# RiskChemi_Sensors.net
KiCad netlist of a schematic drawn in Altium Designer
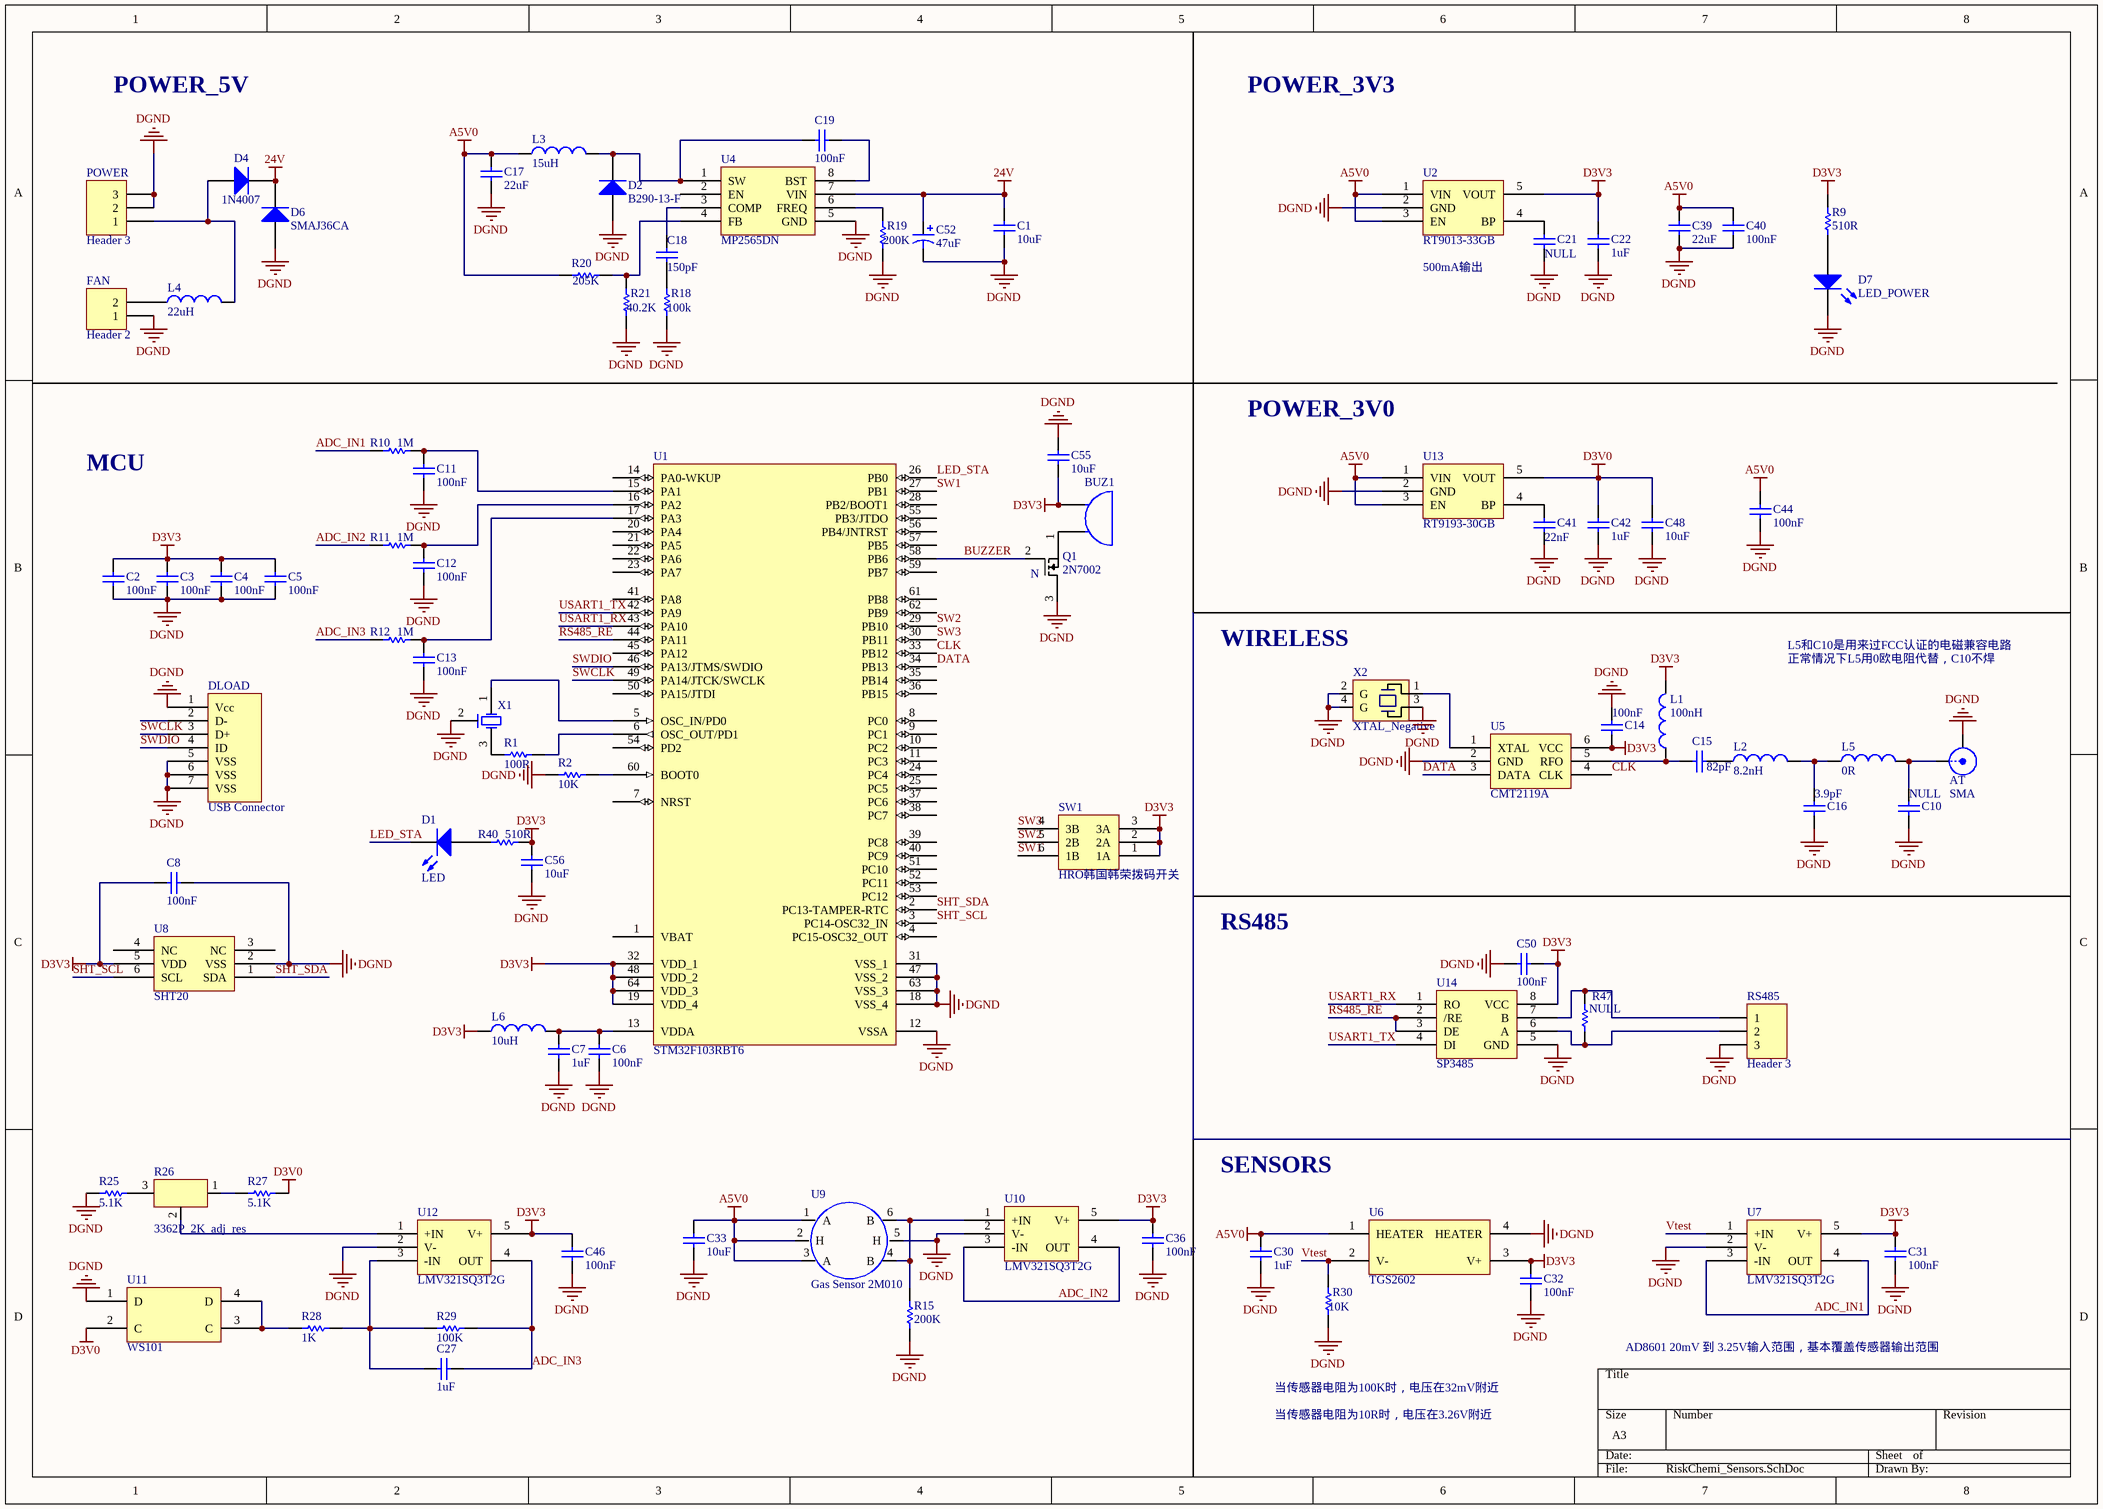
[diagram p0: RiskChemi_Sensors.SchDoc]

(export (version "E")
  (design (tool "Eeschema 10.0.6"))
  (components
    (comp (ref "AT")
      (value "SMA")
      (footprint "SMA")
      (description "SMB Straight Connector")
      (fields (field (name "PUBLISHER") "Altium Limited"))
      (libsource (lib "Miscellaneous Connectors") (part "SMB"))
    )
    (comp (ref "BUZ1")
      (value "BUZZER 0905 through hole")
      (footprint "BUZ0905")
      (description "Buzzer")
      (libsource (lib "杂元件库") (part "BUZZER"))
    )
    (comp (ref "C1")
      (value "10uF")
      (footprint "0805")
      (description "Capacitor,50V")
      (fields (field (name "PUBLISHER") "Altium Limited"))
      (libsource (lib "Miscellaneous Devices") (part "Cap"))
    )
    (comp (ref "C2")
      (value "100nF")
      (footprint "BinFeng:0603")
      (description "Capacitor")
      (fields (field (name "PUBLISHER") "Altium Limited"))
      (libsource (lib "Miscellaneous Devices") (part "Cap"))
    )
    (comp (ref "C3")
      (value "100nF")
      (footprint "BinFeng:0603")
      (description "Capacitor")
      (fields (field (name "PUBLISHER") "Altium Limited"))
      (libsource (lib "Miscellaneous Devices") (part "Cap"))
    )
    (comp (ref "C4")
      (value "100nF")
      (footprint "BinFeng:0603")
      (description "Capacitor")
      (fields (field (name "PUBLISHER") "Altium Limited"))
      (libsource (lib "Miscellaneous Devices") (part "Cap"))
    )
    (comp (ref "C5")
      (value "100nF")
      (footprint "BinFeng:0603")
      (description "Capacitor")
      (fields (field (name "PUBLISHER") "Altium Limited"))
      (libsource (lib "Miscellaneous Devices") (part "Cap"))
    )
    (comp (ref "C6")
      (value "100nF")
      (footprint "BinFeng:0603")
      (description "Capacitor")
      (fields (field (name "PUBLISHER") "Altium Limited"))
      (libsource (lib "Miscellaneous Devices") (part "Cap"))
    )
    (comp (ref "C7")
      (value "1uF")
      (footprint "BinFeng:0603")
      (description "Capacitor")
      (fields (field (name "PUBLISHER") "Altium Limited"))
      (libsource (lib "Miscellaneous Devices") (part "Cap"))
    )
    (comp (ref "C8")
      (value "100nF")
      (footprint "BinFeng:0603")
      (description "Capacitor")
      (fields (field (name "PUBLISHER") "Altium Limited"))
      (libsource (lib "Miscellaneous Devices") (part "Cap"))
    )
    (comp (ref "C10")
      (value "NULL")
      (footprint "BinFeng:0402")
      (description "Capacitor")
      (fields (field (name "PUBLISHER") "Altium Limited"))
      (libsource (lib "Miscellaneous Devices") (part "Cap"))
    )
    (comp (ref "C11")
      (value "100nF")
      (footprint "BinFeng:0603")
      (description "Capacitor")
      (fields (field (name "PUBLISHER") "Altium Limited"))
      (libsource (lib "Miscellaneous Devices") (part "Cap"))
    )
    (comp (ref "C12")
      (value "100nF")
      (footprint "BinFeng:0603")
      (description "Capacitor")
      (fields (field (name "PUBLISHER") "Altium Limited"))
      (libsource (lib "Miscellaneous Devices") (part "Cap"))
    )
    (comp (ref "C13")
      (value "100nF")
      (footprint "BinFeng:0603")
      (description "Capacitor")
      (fields (field (name "PUBLISHER") "Altium Limited"))
      (libsource (lib "Miscellaneous Devices") (part "Cap"))
    )
    (comp (ref "C14")
      (value "100nF")
      (footprint "BinFeng:0402")
      (description "Capacitor")
      (fields (field (name "PUBLISHER") "Altium Limited"))
      (libsource (lib "Miscellaneous Devices") (part "Cap"))
    )
    (comp (ref "C15")
      (value "82pF")
      (footprint "BinFeng:0402")
      (description "Capacitor")
      (fields (field (name "PUBLISHER") "Altium Limited"))
      (libsource (lib "Miscellaneous Devices") (part "Cap"))
    )
    (comp (ref "C16")
      (value "3.9pF")
      (footprint "BinFeng:0402")
      (description "Capacitor")
      (fields (field (name "PUBLISHER") "Altium Limited"))
      (libsource (lib "Miscellaneous Devices") (part "Cap"))
    )
    (comp (ref "C17")
      (value "22uF")
      (footprint "0805")
      (description "Capacitor,50V")
      (fields (field (name "PUBLISHER") "Altium Limited"))
      (libsource (lib "Miscellaneous Devices") (part "Cap"))
    )
    (comp (ref "C18")
      (value "150pF")
      (footprint "BinFeng:0603")
      (description "Capacitor")
      (fields (field (name "PUBLISHER") "Altium Limited"))
      (libsource (lib "Miscellaneous Devices") (part "Cap"))
    )
    (comp (ref "C19")
      (value "100nF")
      (footprint "BinFeng:0603")
      (description "Capacitor")
      (fields (field (name "PUBLISHER") "Altium Limited"))
      (libsource (lib "Miscellaneous Devices") (part "Cap"))
    )
    (comp (ref "C21")
      (value "NULL")
      (footprint "BinFeng:0402")
      (description "Capacitor")
      (fields (field (name "PUBLISHER") "Altium Limited"))
      (libsource (lib "Miscellaneous Devices") (part "Cap"))
    )
    (comp (ref "C22")
      (value "1uF")
      (footprint "BinFeng:0402")
      (description "Capacitor")
      (fields (field (name "PUBLISHER") "Altium Limited"))
      (libsource (lib "Miscellaneous Devices") (part "Cap"))
    )
    (comp (ref "C27")
      (value "1uF")
      (footprint "BinFeng:0603")
      (description "Capacitor")
      (fields (field (name "PUBLISHER") "Altium Limited"))
      (libsource (lib "Miscellaneous Devices") (part "Cap"))
    )
    (comp (ref "C30")
      (value "1uF")
      (footprint "BinFeng:0603")
      (description "Capacitor")
      (fields (field (name "PUBLISHER") "Altium Limited"))
      (libsource (lib "Miscellaneous Devices") (part "Cap"))
    )
    (comp (ref "C31")
      (value "100nF")
      (footprint "BinFeng:0603")
      (description "Capacitor")
      (fields (field (name "PUBLISHER") "Altium Limited"))
      (libsource (lib "Miscellaneous Devices") (part "Cap"))
    )
    (comp (ref "C32")
      (value "100nF")
      (footprint "BinFeng:0603")
      (description "Capacitor")
      (fields (field (name "PUBLISHER") "Altium Limited"))
      (libsource (lib "Miscellaneous Devices") (part "Cap"))
    )
    (comp (ref "C33")
      (value "10uF")
      (footprint "0805")
      (description "Capacitor")
      (fields (field (name "PUBLISHER") "Altium Limited"))
      (libsource (lib "Miscellaneous Devices") (part "Cap"))
    )
    (comp (ref "C36")
      (value "100nF")
      (footprint "BinFeng:0603")
      (description "Capacitor")
      (fields (field (name "PUBLISHER") "Altium Limited"))
      (libsource (lib "Miscellaneous Devices") (part "Cap"))
    )
    (comp (ref "C39")
      (value "22uF")
      (footprint "1206")
      (description "Capacitor")
      (fields (field (name "PUBLISHER") "Altium Limited"))
      (libsource (lib "Miscellaneous Devices") (part "Cap"))
    )
    (comp (ref "C40")
      (value "100nF")
      (footprint "BinFeng:0402")
      (description "Capacitor")
      (fields (field (name "PUBLISHER") "Altium Limited"))
      (libsource (lib "Miscellaneous Devices") (part "Cap"))
    )
    (comp (ref "C41")
      (value "22nF")
      (footprint "BinFeng:0402")
      (description "Capacitor")
      (fields (field (name "PUBLISHER") "Altium Limited"))
      (libsource (lib "Miscellaneous Devices") (part "Cap"))
    )
    (comp (ref "C42")
      (value "1uF")
      (footprint "BinFeng:0402")
      (description "Capacitor")
      (fields (field (name "PUBLISHER") "Altium Limited"))
      (libsource (lib "Miscellaneous Devices") (part "Cap"))
    )
    (comp (ref "C44")
      (value "100nF")
      (footprint "BinFeng:0402")
      (description "Capacitor")
      (fields (field (name "PUBLISHER") "Altium Limited"))
      (libsource (lib "Miscellaneous Devices") (part "Cap"))
    )
    (comp (ref "C46")
      (value "100nF")
      (footprint "BinFeng:0603")
      (description "Capacitor")
      (fields (field (name "PUBLISHER") "Altium Limited"))
      (libsource (lib "Miscellaneous Devices") (part "Cap"))
    )
    (comp (ref "C48")
      (value "10uF")
      (footprint "0805")
      (description "Capacitor")
      (fields (field (name "PUBLISHER") "Altium Limited"))
      (libsource (lib "Miscellaneous Devices") (part "Cap"))
    )
    (comp (ref "C50")
      (value "100nF")
      (footprint "BinFeng:0603")
      (description "Capacitor")
      (fields (field (name "PUBLISHER") "Altium Limited"))
      (libsource (lib "Miscellaneous Devices") (part "Cap"))
    )
    (comp (ref "C52")
      (value "47uF")
      (footprint "cap_pol_8*10.2")
      (description "Polarized Capacitor (Radial)")
      (fields (field (name "PUBLISHER") "Altium Limited"))
      (libsource (lib "Miscellaneous Devices") (part "Cap Pol1"))
    )
    (comp (ref "C55")
      (value "10uF")
      (footprint "0805")
      (description "Capacitor")
      (fields (field (name "PUBLISHER") "Altium Limited"))
      (libsource (lib "Miscellaneous Devices") (part "Cap"))
    )
    (comp (ref "C56")
      (value "10uF")
      (footprint "0805")
      (description "Capacitor")
      (fields (field (name "PUBLISHER") "Altium Limited"))
      (libsource (lib "Miscellaneous Devices") (part "Cap"))
    )
    (comp (ref "D1")
      (value "LED")
      (footprint "1206_LED")
      (description "Typical INFRARED GaAs LED")
      (fields (field (name "PUBLISHER") "Altium Limited"))
      (libsource (lib "Miscellaneous Devices") (part "LED0"))
    )
    (comp (ref "D2")
      (value "B290-13-F")
      (footprint "B290")
      (description "Default Diode")
      (fields (field (name "PUBLISHER") "Altium Limited"))
      (libsource (lib "Miscellaneous Devices") (part "Diode"))
    )
    (comp (ref "D4")
      (value "1N4007")
      (footprint "6032_pol")
      (description "1 Amp General Purpose Rectifier")
      (fields (field (name "PUBLISHER") "Altium Limited"))
      (libsource (lib "Miscellaneous Devices") (part "Diode 1N4007"))
    )
    (comp (ref "D6")
      (value "SMAJ36CA")
      (footprint "B290")
      (description "1 Amp General Purpose Rectifier")
      (fields (field (name "PUBLISHER") "Altium Limited"))
      (libsource (lib "Miscellaneous Devices") (part "Diode 1N4007"))
    )
    (comp (ref "D7")
      (value "LED_POWER")
      (footprint "1206_LED")
      (description "Typical INFRARED GaAs LED")
      (fields (field (name "PUBLISHER") "Altium Limited"))
      (libsource (lib "Miscellaneous Devices") (part "LED0"))
    )
    (comp (ref "DLOAD")
      (value "USB Connector")
      (footprint "Mini_USB")
      (libsource (lib "BinFeng_Connectors") (part "Component_1"))
    )
    (comp (ref "FAN")
      (value "Header 2")
      (footprint "HDR1X2")
      (description "Header, 2-Pin")
      (fields (field (name "PUBLISHER") "Altium Limited"))
      (libsource (lib "Miscellaneous Connectors") (part "Header 2"))
    )
    (comp (ref "L1")
      (value "100nH")
      (footprint "0603C")
      (description "Inductor")
      (fields (field (name "PUBLISHER") "Altium Limited"))
      (libsource (lib "Miscellaneous Devices") (part "Inductor"))
    )
    (comp (ref "L2")
      (value "8.2nH")
      (footprint "0603C")
      (description "Inductor")
      (fields (field (name "PUBLISHER") "Altium Limited"))
      (libsource (lib "Miscellaneous Devices") (part "Inductor"))
    )
    (comp (ref "L3")
      (value "15uH")
      (footprint "4*4 Inductor")
      (description "Inductor, 1A")
      (fields (field (name "PUBLISHER") "Altium Limited"))
      (libsource (lib "Miscellaneous Devices") (part "Inductor"))
    )
    (comp (ref "L4")
      (value "22uH")
      (footprint "10*10Inductor")
      (description "Inductor, 1A")
      (fields (field (name "PUBLISHER") "Altium Limited"))
      (libsource (lib "Miscellaneous Devices") (part "Inductor"))
    )
    (comp (ref "L5")
      (value "0R")
      (footprint "0603C")
      (description "Inductor")
      (fields (field (name "PUBLISHER") "Altium Limited"))
      (libsource (lib "Miscellaneous Devices") (part "Inductor"))
    )
    (comp (ref "L6")
      (value "10uH")
      (footprint "0805")
      (description "Inductor")
      (fields (field (name "PUBLISHER") "Altium Limited"))
      (libsource (lib "Miscellaneous Devices") (part "Inductor"))
    )
    (comp (ref "POWER")
      (value "Header 3")
      (footprint "KR_1x2H")
      (description "Header, 3-Pin")
      (fields (field (name "PUBLISHER") "Altium Limited"))
      (libsource (lib "Miscellaneous Connectors") (part "Header 3"))
    )
    (comp (ref "Q1") (value "2N7002") (footprint "2N7002") (libsource (lib "seeder") (part "N-MOSFET")))
    (comp (ref "R1")
      (value "100R")
      (footprint "BinFeng:0603")
      (description "Resistor")
      (fields (field (name "PUBLISHER") "Altium Limited"))
      (libsource (lib "Miscellaneous Devices") (part "Res1"))
    )
    (comp (ref "R2")
      (value "10K")
      (footprint "BinFeng:0603")
      (description "Resistor")
      (fields (field (name "PUBLISHER") "Altium Limited"))
      (libsource (lib "Miscellaneous Devices") (part "Res1"))
    )
    (comp (ref "R9")
      (value "510R")
      (footprint "BinFeng:0603")
      (description "Resistor")
      (fields (field (name "PUBLISHER") "Altium Limited"))
      (libsource (lib "Miscellaneous Devices") (part "Res1"))
    )
    (comp (ref "R10")
      (value "1M")
      (footprint "BinFeng:0603")
      (description "Resistor")
      (fields (field (name "PUBLISHER") "Altium Limited"))
      (libsource (lib "Miscellaneous Devices") (part "Res1"))
    )
    (comp (ref "R11")
      (value "1M")
      (footprint "BinFeng:0603")
      (description "Resistor")
      (fields (field (name "PUBLISHER") "Altium Limited"))
      (libsource (lib "Miscellaneous Devices") (part "Res1"))
    )
    (comp (ref "R12")
      (value "1M")
      (footprint "BinFeng:0603")
      (description "Resistor")
      (fields (field (name "PUBLISHER") "Altium Limited"))
      (libsource (lib "Miscellaneous Devices") (part "Res1"))
    )
    (comp (ref "R15")
      (value "200K")
      (footprint "BinFeng:0603C")
      (description "Resistor")
      (fields (field (name "Comment") "Res1") (field (name "PUBLISHER") "Altium Limited"))
      (libsource (lib "Miscellaneous Devices") (part "Res1"))
    )
    (comp (ref "R18")
      (value "100k")
      (footprint "BinFeng:0603")
      (description "Resistor")
      (fields (field (name "PUBLISHER") "Altium Limited"))
      (libsource (lib "Miscellaneous Devices") (part "Res1"))
    )
    (comp (ref "R19")
      (value "200K")
      (footprint "BinFeng:0402")
      (description "Resistor")
      (fields (field (name "PUBLISHER") "Altium Limited"))
      (libsource (lib "Miscellaneous Devices") (part "Res1"))
    )
    (comp (ref "R20")
      (value "205K")
      (footprint "BinFeng:0603")
      (description "Resistor")
      (fields (field (name "PUBLISHER") "Altium Limited"))
      (libsource (lib "Miscellaneous Devices") (part "Res1"))
    )
    (comp (ref "R21")
      (value "40.2K")
      (footprint "BinFeng:0603")
      (description "Resistor")
      (fields (field (name "PUBLISHER") "Altium Limited"))
      (libsource (lib "Miscellaneous Devices") (part "Res1"))
    )
    (comp (ref "R25")
      (value "5.1K")
      (footprint "BinFeng:0603")
      (description "Resistor")
      (fields (field (name "PUBLISHER") "Altium Limited"))
      (libsource (lib "Miscellaneous Devices") (part "Res1"))
    )
    (comp (ref "R26")
      (value "3362P_2K_adj_res")
      (footprint "res_adj")
      (libsource (lib "BinFeng_IC") (part "res_adj"))
    )
    (comp (ref "R27")
      (value "5.1K")
      (footprint "BinFeng:0603")
      (description "Resistor")
      (fields (field (name "PUBLISHER") "Altium Limited"))
      (libsource (lib "Miscellaneous Devices") (part "Res1"))
    )
    (comp (ref "R28")
      (value "1K")
      (footprint "BinFeng:0603")
      (description "Resistor")
      (fields (field (name "PUBLISHER") "Altium Limited"))
      (libsource (lib "Miscellaneous Devices") (part "Res1"))
    )
    (comp (ref "R29")
      (value "100K")
      (footprint "BinFeng:0603")
      (description "Resistor")
      (fields (field (name "PUBLISHER") "Altium Limited"))
      (libsource (lib "Miscellaneous Devices") (part "Res1"))
    )
    (comp (ref "R30")
      (value "10K")
      (footprint "BinFeng:0603")
      (description "Resistor")
      (fields (field (name "PUBLISHER") "Altium Limited"))
      (libsource (lib "Miscellaneous Devices") (part "Res1"))
    )
    (comp (ref "R40")
      (value "510R")
      (footprint "BinFeng:0603")
      (description "Resistor")
      (fields (field (name "PUBLISHER") "Altium Limited"))
      (libsource (lib "Miscellaneous Devices") (part "Res1"))
    )
    (comp (ref "R47")
      (value "NULL")
      (footprint "BinFeng:0603")
      (description "Resistor")
      (fields (field (name "PUBLISHER") "Altium Limited"))
      (libsource (lib "Miscellaneous Devices") (part "Res1"))
    )
    (comp (ref "RS485")
      (value "Header 3")
      (footprint "KR_1x2H")
      (description "Header, 3-Pin")
      (fields (field (name "PUBLISHER") "Altium Limited"))
      (libsource (lib "") (part "Header 3_1"))
    )
    (comp (ref "SW1")
      (value "HRO韩国韩荣拨码开关")
      (footprint "SW_6P_HRO")
      (libsource (lib "BinFeng_IC") (part "SW_6P"))
    )
    (comp (ref "U1")
      (value "STM32F103RBT6")
      (footprint "LQFP64_N")
      (description "STM32 ARM-based 32-bit MCU with 64 Kbytes Flash, 64-pin LQFP, Industrial Temperature")
      (fields (field (name "PUBLISHER") "Altium Limited"))
      (libsource (lib "ST Microcontroller 32-Bit STM32") (part "STM32F103R8T6"))
    )
    (comp (ref "U2")
      (value "RT9013-33GB")
      (footprint "SOT-23-5")
      (libsource (lib "BinFeng_IC") (part "RT9193"))
    )
    (comp (ref "U4")
      (value "MP2565DN")
      (footprint "so-8")
      (description "DCDC 4.5V~28V input 1.8V ~5V output low power")
      (libsource (lib "BinFeng_IC") (part "MP1584"))
    )
    (comp (ref "U5")
      (value "CMT2119A")
      (footprint "sot23-6")
      (libsource (lib "BinFeng_IC") (part "CMT2119A"))
    )
    (comp (ref "U6")
      (value "TGS2602")
      (footprint "Gas Sensor TGS2602 Slot")
      (description "VOC sensor")
      (libsource (lib "BinFeng_IC") (part "TGS2602"))
    )
    (comp (ref "U7")
      (value "LMV321SQ3T2G")
      (footprint "SC-70-5")
      (libsource (lib "BinFeng_IC") (part "LMV321SQ3T2G"))
    )
    (comp (ref "U8") (value "SHT20") (footprint "SHT20") (libsource (lib "BinFeng_IC") (part "SHT20")))
    (comp (ref "U9")
      (value "Gas Sensor 2M010")
      (footprint "Gas Sensor 2M010 Slot")
      (libsource (lib "BinFeng_IC") (part "Gas Sensor"))
    )
    (comp (ref "U10")
      (value "LMV321SQ3T2G")
      (footprint "SC-70-5")
      (libsource (lib "BinFeng_IC") (part "LMV321SQ3T2G"))
    )
    (comp (ref "U11")
      (value "WS101")
      (footprint "Gas_Sensor_WS101_Slot")
      (libsource (lib "BinFeng_IC") (part "Gas Sensor_WS101"))
    )
    (comp (ref "U12")
      (value "LMV321SQ3T2G")
      (footprint "SC-70-5")
      (libsource (lib "BinFeng_IC") (part "LMV321SQ3T2G"))
    )
    (comp (ref "U13")
      (value "RT9193-30GB")
      (footprint "SOT-23-5")
      (libsource (lib "BinFeng_IC") (part "RT9193"))
    )
    (comp (ref "U14") (value "SP3485") (footprint "SO-8N") (libsource (lib "BinFeng_IC") (part "SP3485")))
    (comp (ref "X1") (value "8M smd") (footprint "8Mhz_XTAL") (libsource (lib "Schlib1") (part "8M smd")))
    (comp (ref "X2")
      (value "XTAL_Negative")
      (footprint "XTAL3225")
      (libsource (lib "BinFeng_IC") (part "XTAL_Negative"))
    )
  )
  (nets
    (net (code "1") (name "/ADC_IN1") (class "Default")
      (node (ref "R10") (pin "1") (pinfunction "1_1") (pintype "passive"))
      (node (ref "U7") (pin "3") (pinfunction "-IN_3") (pintype "passive"))
      (node (ref "U7") (pin "4") (pinfunction "OUT_4") (pintype "passive"))
    )
    (net (code "2") (name "/ADC_IN2") (class "Default")
      (node (ref "R11") (pin "1") (pinfunction "1_1") (pintype "passive"))
      (node (ref "U10") (pin "3") (pinfunction "-IN_3") (pintype "passive"))
      (node (ref "U10") (pin "4") (pinfunction "OUT_4") (pintype "passive"))
    )
    (net (code "3") (name "/ADC_IN3") (class "Default")
      (node (ref "C27") (pin "1") (pinfunction "1_1") (pintype "passive"))
      (node (ref "R12") (pin "1") (pinfunction "1_1") (pintype "passive"))
      (node (ref "R29") (pin "2") (pinfunction "2_2") (pintype "passive"))
      (node (ref "U12") (pin "4") (pinfunction "OUT_4") (pintype "passive"))
    )
    (net (code "4") (name "/BUZZER") (class "Default")
      (node (ref "Q1") (pin "2") (pinfunction "G_2") (pintype "passive"))
      (node (ref "U1") (pin "58") (pinfunction "PB6_58") (pintype "bidirectional"))
    )
    (net (code "5") (name "/CLK") (class "Default")
      (node (ref "U1") (pin "33") (pinfunction "PB12_33") (pintype "bidirectional"))
      (node (ref "U5") (pin "4") (pinfunction "CLK_4") (pintype "passive"))
    )
    (net (code "6") (name "/DATA") (class "Default")
      (node (ref "U1") (pin "34") (pinfunction "PB13_34") (pintype "bidirectional"))
      (node (ref "U5") (pin "3") (pinfunction "DATA_3") (pintype "passive"))
    )
    (net (code "7") (name "/LED_STA") (class "Default")
      (node (ref "D1") (pin "2") (pinfunction "K_2") (pintype "passive"))
      (node (ref "U1") (pin "26") (pinfunction "PB0_26") (pintype "bidirectional"))
    )
    (net (code "8") (name "/RS485_RE") (class "Default")
      (node (ref "U1") (pin "44") (pinfunction "PA11_44") (pintype "bidirectional"))
      (node (ref "U14") (pin "2") (pinfunction "/RE_2") (pintype "passive"))
      (node (ref "U14") (pin "3") (pinfunction "DE_3") (pintype "passive"))
    )
    (net (code "9") (name "/SHT_SCL") (class "Default")
      (node (ref "U1") (pin "3") (pinfunction "PC14-OSC32_IN_3") (pintype "bidirectional"))
      (node (ref "U8") (pin "6") (pinfunction "SCL_6") (pintype "passive"))
    )
    (net (code "10") (name "/SHT_SDA") (class "Default")
      (node (ref "U1") (pin "2") (pinfunction "PC13-TAMPER-RTC_2") (pintype "bidirectional"))
      (node (ref "U8") (pin "1") (pinfunction "SDA_1") (pintype "passive"))
    )
    (net (code "11") (name "/SW1") (class "Default")
      (node (ref "SW1") (pin "6") (pinfunction "1B_6") (pintype "passive"))
      (node (ref "U1") (pin "27") (pinfunction "PB1_27") (pintype "bidirectional"))
    )
    (net (code "12") (name "/SW2") (class "Default")
      (node (ref "SW1") (pin "5") (pinfunction "2B_5") (pintype "passive"))
      (node (ref "U1") (pin "29") (pinfunction "PB10_29") (pintype "bidirectional"))
    )
    (net (code "13") (name "/SW3") (class "Default")
      (node (ref "SW1") (pin "4") (pinfunction "3B_4") (pintype "passive"))
      (node (ref "U1") (pin "30") (pinfunction "PB11_30") (pintype "bidirectional"))
    )
    (net (code "14") (name "/SWCLK") (class "Default")
      (node (ref "DLOAD") (pin "3") (pinfunction "D+_3") (pintype "passive"))
      (node (ref "U1") (pin "49") (pinfunction "PA14/JTCK/SWCLK_49") (pintype "bidirectional"))
    )
    (net (code "15") (name "/SWDIO") (class "Default")
      (node (ref "DLOAD") (pin "4") (pinfunction "ID_4") (pintype "passive"))
      (node (ref "U1") (pin "46") (pinfunction "PA13/JTMS/SWDIO_46") (pintype "bidirectional"))
    )
    (net (code "16") (name "/USART1_RX") (class "Default")
      (node (ref "U1") (pin "43") (pinfunction "PA10_43") (pintype "bidirectional"))
      (node (ref "U14") (pin "1") (pinfunction "RO_1") (pintype "passive"))
    )
    (net (code "17") (name "/USART1_TX") (class "Default")
      (node (ref "U1") (pin "42") (pinfunction "PA9_42") (pintype "bidirectional"))
      (node (ref "U14") (pin "4") (pinfunction "DI_4") (pintype "passive"))
    )
    (net (code "18") (name "/Vtest") (class "Default")
      (node (ref "R30") (pin "2") (pinfunction "2_2") (pintype "passive"))
      (node (ref "U6") (pin "2") (pinfunction "V-_2") (pintype "passive"))
      (node (ref "U7") (pin "1") (pinfunction "+IN_1") (pintype "passive"))
    )
    (net (code "19") (name "24V") (class "Default")
      (node (ref "C1") (pin "2") (pinfunction "2_2") (pintype "passive"))
      (node (ref "C52") (pin "1") (pinfunction "1_1") (pintype "passive"))
      (node (ref "D4") (pin "2") (pinfunction "K_2") (pintype "passive"))
      (node (ref "D6") (pin "2") (pinfunction "K_2") (pintype "passive"))
      (node (ref "U4") (pin "7") (pinfunction "VIN_7") (pintype "passive"))
    )
    (net (code "20") (name "A5V0") (class "Default")
      (node (ref "C17") (pin "2") (pinfunction "2_2") (pintype "passive"))
      (node (ref "C30") (pin "2") (pinfunction "2_2") (pintype "passive"))
      (node (ref "C33") (pin "2") (pinfunction "2_2") (pintype "passive"))
      (node (ref "C39") (pin "1") (pinfunction "1_1") (pintype "passive"))
      (node (ref "C40") (pin "2") (pinfunction "2_2") (pintype "passive"))
      (node (ref "C44") (pin "2") (pinfunction "2_2") (pintype "passive"))
      (node (ref "L3") (pin "1") (pinfunction "1_1") (pintype "passive"))
      (node (ref "R20") (pin "2") (pinfunction "2_2") (pintype "passive"))
      (node (ref "U13") (pin "1") (pinfunction "VIN_1") (pintype "passive"))
      (node (ref "U13") (pin "3") (pinfunction "EN_3") (pintype "passive"))
      (node (ref "U2") (pin "1") (pinfunction "VIN_1") (pintype "passive"))
      (node (ref "U2") (pin "3") (pinfunction "EN_3") (pintype "passive"))
      (node (ref "U6") (pin "1") (pinfunction "HEATER_1") (pintype "passive"))
      (node (ref "U9") (pin "1") (pinfunction "A_1") (pintype "passive"))
      (node (ref "U9") (pin "2") (pinfunction "H_2") (pintype "passive"))
      (node (ref "U9") (pin "3") (pinfunction "A_3") (pintype "passive"))
    )
    (net (code "21") (name "D3V0") (class "Default")
      (node (ref "C42") (pin "2") (pinfunction "2_2") (pintype "passive"))
      (node (ref "C48") (pin "2") (pinfunction "2_2") (pintype "passive"))
      (node (ref "R27") (pin "2") (pinfunction "2_2") (pintype "passive"))
      (node (ref "U11") (pin "2") (pinfunction "C_2") (pintype "passive"))
      (node (ref "U13") (pin "5") (pinfunction "VOUT_5") (pintype "passive"))
    )
    (net (code "22") (name "D3V3") (class "Default")
      (node (ref "BUZ1") (pin "1") (pinfunction "A_1") (pintype "passive"))
      (node (ref "C14") (pin "2") (pinfunction "2_2") (pintype "passive"))
      (node (ref "C2") (pin "2") (pinfunction "2_2") (pintype "passive"))
      (node (ref "C22") (pin "2") (pinfunction "2_2") (pintype "passive"))
      (node (ref "C3") (pin "2") (pinfunction "2_2") (pintype "passive"))
      (node (ref "C31") (pin "2") (pinfunction "2_2") (pintype "passive"))
      (node (ref "C32") (pin "2") (pinfunction "2_2") (pintype "passive"))
      (node (ref "C36") (pin "2") (pinfunction "2_2") (pintype "passive"))
      (node (ref "C4") (pin "2") (pinfunction "2_2") (pintype "passive"))
      (node (ref "C46") (pin "2") (pinfunction "2_2") (pintype "passive"))
      (node (ref "C5") (pin "2") (pinfunction "2_2") (pintype "passive"))
      (node (ref "C50") (pin "2") (pinfunction "2_2") (pintype "passive"))
      (node (ref "C55") (pin "2") (pinfunction "2_2") (pintype "passive"))
      (node (ref "C56") (pin "2") (pinfunction "2_2") (pintype "passive"))
      (node (ref "C8") (pin "2") (pinfunction "2_2") (pintype "passive"))
      (node (ref "L1") (pin "2") (pinfunction "2_2") (pintype "passive"))
      (node (ref "L6") (pin "1") (pinfunction "1_1") (pintype "passive"))
      (node (ref "R40") (pin "2") (pinfunction "2_2") (pintype "passive"))
      (node (ref "R9") (pin "2") (pinfunction "2_2") (pintype "passive"))
      (node (ref "SW1") (pin "1") (pinfunction "1A_1") (pintype "passive"))
      (node (ref "SW1") (pin "2") (pinfunction "2A_2") (pintype "passive"))
      (node (ref "SW1") (pin "3") (pinfunction "3A_3") (pintype "passive"))
      (node (ref "U1") (pin "19") (pinfunction "VDD_4_19") (pintype "power_in"))
      (node (ref "U1") (pin "32") (pinfunction "VDD_1_32") (pintype "power_in"))
      (node (ref "U1") (pin "48") (pinfunction "VDD_2_48") (pintype "power_in"))
      (node (ref "U1") (pin "64") (pinfunction "VDD_3_64") (pintype "power_in"))
      (node (ref "U10") (pin "5") (pinfunction "V+_5") (pintype "passive"))
      (node (ref "U12") (pin "5") (pinfunction "V+_5") (pintype "passive"))
      (node (ref "U14") (pin "8") (pinfunction "VCC_8") (pintype "passive"))
      (node (ref "U2") (pin "5") (pinfunction "VOUT_5") (pintype "passive"))
      (node (ref "U5") (pin "6") (pinfunction "VCC_6") (pintype "passive"))
      (node (ref "U6") (pin "3") (pinfunction "V+_3") (pintype "passive"))
      (node (ref "U7") (pin "5") (pinfunction "V+_5") (pintype "passive"))
      (node (ref "U8") (pin "5") (pinfunction "VDD_5") (pintype "passive"))
    )
    (net (code "23") (name "DGND") (class "Default")
      (node (ref "AT") (pin "2") (pinfunction "Y_2") (pintype "passive"))
      (node (ref "C1") (pin "1") (pinfunction "1_1") (pintype "passive"))
      (node (ref "C10") (pin "1") (pinfunction "1_1") (pintype "passive"))
      (node (ref "C11") (pin "2") (pinfunction "2_2") (pintype "passive"))
      (node (ref "C12") (pin "1") (pinfunction "1_1") (pintype "passive"))
      (node (ref "C13") (pin "1") (pinfunction "1_1") (pintype "passive"))
      (node (ref "C14") (pin "1") (pinfunction "1_1") (pintype "passive"))
      (node (ref "C16") (pin "1") (pinfunction "1_1") (pintype "passive"))
      (node (ref "C17") (pin "1") (pinfunction "1_1") (pintype "passive"))
      (node (ref "C2") (pin "1") (pinfunction "1_1") (pintype "passive"))
      (node (ref "C21") (pin "1") (pinfunction "1_1") (pintype "passive"))
      (node (ref "C22") (pin "1") (pinfunction "1_1") (pintype "passive"))
      (node (ref "C3") (pin "1") (pinfunction "1_1") (pintype "passive"))
      (node (ref "C30") (pin "1") (pinfunction "1_1") (pintype "passive"))
      (node (ref "C31") (pin "1") (pinfunction "1_1") (pintype "passive"))
      (node (ref "C32") (pin "1") (pinfunction "1_1") (pintype "passive"))
      (node (ref "C33") (pin "1") (pinfunction "1_1") (pintype "passive"))
      (node (ref "C36") (pin "1") (pinfunction "1_1") (pintype "passive"))
      (node (ref "C39") (pin "2") (pinfunction "2_2") (pintype "passive"))
      (node (ref "C4") (pin "1") (pinfunction "1_1") (pintype "passive"))
      (node (ref "C40") (pin "1") (pinfunction "1_1") (pintype "passive"))
      (node (ref "C41") (pin "1") (pinfunction "1_1") (pintype "passive"))
      (node (ref "C42") (pin "1") (pinfunction "1_1") (pintype "passive"))
      (node (ref "C44") (pin "1") (pinfunction "1_1") (pintype "passive"))
      (node (ref "C46") (pin "1") (pinfunction "1_1") (pintype "passive"))
      (node (ref "C48") (pin "1") (pinfunction "1_1") (pintype "passive"))
      (node (ref "C5") (pin "1") (pinfunction "1_1") (pintype "passive"))
      (node (ref "C50") (pin "1") (pinfunction "1_1") (pintype "passive"))
      (node (ref "C52") (pin "2") (pinfunction "2_2") (pintype "passive"))
      (node (ref "C55") (pin "1") (pinfunction "1_1") (pintype "passive"))
      (node (ref "C56") (pin "1") (pinfunction "1_1") (pintype "passive"))
      (node (ref "C6") (pin "1") (pinfunction "1_1") (pintype "passive"))
      (node (ref "C7") (pin "1") (pinfunction "1_1") (pintype "passive"))
      (node (ref "C8") (pin "1") (pinfunction "1_1") (pintype "passive"))
      (node (ref "D2") (pin "1") (pinfunction "A_1") (pintype "passive"))
      (node (ref "D6") (pin "1") (pinfunction "A_1") (pintype "passive"))
      (node (ref "D7") (pin "2") (pinfunction "K_2") (pintype "passive"))
      (node (ref "DLOAD") (pin "1") (pinfunction "Vcc_1") (pintype "passive"))
      (node (ref "DLOAD") (pin "5") (pinfunction "VSS_5") (pintype "passive"))
      (node (ref "DLOAD") (pin "6") (pinfunction "VSS_6") (pintype "passive"))
      (node (ref "DLOAD") (pin "7") (pinfunction "VSS_7") (pintype "passive"))
      (node (ref "FAN") (pin "1") (pinfunction "1_1") (pintype "passive"))
      (node (ref "POWER") (pin "2") (pinfunction "2_2") (pintype "passive"))
      (node (ref "POWER") (pin "3") (pinfunction "3_3") (pintype "passive"))
      (node (ref "Q1") (pin "3") (pinfunction "S_3") (pintype "passive"))
      (node (ref "R15") (pin "2") (pinfunction "2_2") (pintype "passive"))
      (node (ref "R18") (pin "1") (pinfunction "1_1") (pintype "passive"))
      (node (ref "R19") (pin "1") (pinfunction "1_1") (pintype "passive"))
      (node (ref "R2") (pin "1") (pinfunction "1_1") (pintype "passive"))
      (node (ref "R21") (pin "1") (pinfunction "1_1") (pintype "passive"))
      (node (ref "R25") (pin "1") (pinfunction "1_1") (pintype "passive"))
      (node (ref "R30") (pin "1") (pinfunction "1_1") (pintype "passive"))
      (node (ref "RS485") (pin "3") (pinfunction "3_3") (pintype "passive"))
      (node (ref "U1") (pin "12") (pinfunction "VSSA_12") (pintype "power_in"))
      (node (ref "U1") (pin "18") (pinfunction "VSS_4_18") (pintype "power_in"))
      (node (ref "U1") (pin "31") (pinfunction "VSS_1_31") (pintype "power_in"))
      (node (ref "U1") (pin "47") (pinfunction "VSS_2_47") (pintype "power_in"))
      (node (ref "U1") (pin "63") (pinfunction "VSS_3_63") (pintype "power_in"))
      (node (ref "U10") (pin "2") (pinfunction "V-_2") (pintype "passive"))
      (node (ref "U11") (pin "1") (pinfunction "D_1") (pintype "passive"))
      (node (ref "U12") (pin "2") (pinfunction "V-_2") (pintype "passive"))
      (node (ref "U13") (pin "2") (pinfunction "GND_2") (pintype "passive"))
      (node (ref "U14") (pin "5") (pinfunction "GND_5") (pintype "passive"))
      (node (ref "U2") (pin "2") (pinfunction "GND_2") (pintype "passive"))
      (node (ref "U4") (pin "5") (pinfunction "GND_5") (pintype "passive"))
      (node (ref "U5") (pin "2") (pinfunction "GND_2") (pintype "passive"))
      (node (ref "U6") (pin "4") (pinfunction "HEATER_4") (pintype "passive"))
      (node (ref "U7") (pin "2") (pinfunction "V-_2") (pintype "passive"))
      (node (ref "U8") (pin "2") (pinfunction "VSS_2") (pintype "passive"))
      (node (ref "U9") (pin "5") (pinfunction "H_5") (pintype "passive"))
      (node (ref "X1") (pin "2") (pinfunction "GND_2") (pintype "passive"))
      (node (ref "X2") (pin "2") (pinfunction "G_2") (pintype "passive"))
      (node (ref "X2") (pin "3") (pintype "passive"))
      (node (ref "X2") (pin "4") (pinfunction "G_4") (pintype "passive"))
    )
    (net (code "24") (name "Net-(AT-X)") (class "Default")
      (node (ref "AT") (pin "1") (pinfunction "X_1") (pintype "passive"))
      (node (ref "C10") (pin "2") (pinfunction "2_2") (pintype "passive"))
      (node (ref "L5") (pin "2") (pinfunction "2_2") (pintype "passive"))
    )
    (net (code "25") (name "Net-(BUZ1-B)") (class "Default")
      (node (ref "BUZ1") (pin "2") (pinfunction "B_2") (pintype "passive"))
      (node (ref "Q1") (pin "1") (pinfunction "D_1") (pintype "passive"))
    )
    (net (code "26") (name "Net-(C15-Pad2)") (class "Default")
      (node (ref "C15") (pin "2") (pinfunction "2_2") (pintype "passive"))
      (node (ref "L2") (pin "1") (pinfunction "1_1") (pintype "passive"))
    )
    (net (code "27") (name "Net-(C16-Pad2)") (class "Default")
      (node (ref "C16") (pin "2") (pinfunction "2_2") (pintype "passive"))
      (node (ref "L2") (pin "2") (pinfunction "2_2") (pintype "passive"))
      (node (ref "L5") (pin "1") (pinfunction "1_1") (pintype "passive"))
    )
    (net (code "28") (name "Net-(C18-Pad2)") (class "Default")
      (node (ref "C18") (pin "2") (pinfunction "2_2") (pintype "passive"))
      (node (ref "R18") (pin "2") (pinfunction "2_2") (pintype "passive"))
    )
    (net (code "29") (name "Net-(D1-A)") (class "Default")
      (node (ref "D1") (pin "1") (pinfunction "A_1") (pintype "passive"))
      (node (ref "R40") (pin "1") (pinfunction "1_1") (pintype "passive"))
    )
    (net (code "30") (name "Net-(D2-K)") (class "Default")
      (node (ref "C19") (pin "2") (pinfunction "2_2") (pintype "passive"))
      (node (ref "D2") (pin "2") (pinfunction "K_2") (pintype "passive"))
      (node (ref "L3") (pin "2") (pinfunction "2_2") (pintype "passive"))
      (node (ref "U4") (pin "1") (pinfunction "SW_1") (pintype "passive"))
    )
    (net (code "31") (name "Net-(D4-A)") (class "Default")
      (node (ref "D4") (pin "1") (pinfunction "A_1") (pintype "passive"))
      (node (ref "L4") (pin "2") (pinfunction "2_2") (pintype "passive"))
      (node (ref "POWER") (pin "1") (pinfunction "1_1") (pintype "passive"))
    )
    (net (code "32") (name "Net-(D7-A)") (class "Default")
      (node (ref "D7") (pin "1") (pinfunction "A_1") (pintype "passive"))
      (node (ref "R9") (pin "1") (pinfunction "1_1") (pintype "passive"))
    )
    (net (code "33") (name "Net-(FAN-Pad2)") (class "Default")
      (node (ref "FAN") (pin "2") (pinfunction "2_2") (pintype "passive"))
      (node (ref "L4") (pin "1") (pinfunction "1_1") (pintype "passive"))
    )
    (net (code "34") (name "Net-(R25-Pad2)") (class "Default")
      (node (ref "R25") (pin "2") (pinfunction "2_2") (pintype "passive"))
      (node (ref "R26") (pin "3") (pintype "passive"))
    )
    (net (code "35") (name "Net-(R26-Pad1)") (class "Default")
      (node (ref "R26") (pin "1") (pintype "passive"))
      (node (ref "R27") (pin "1") (pinfunction "1_1") (pintype "passive"))
    )
    (net (code "36") (name "Net-(R28-Pad1)") (class "Default")
      (node (ref "R28") (pin "1") (pinfunction "1_1") (pintype "passive"))
      (node (ref "U11") (pin "3") (pinfunction "C_3") (pintype "passive"))
      (node (ref "U11") (pin "4") (pinfunction "D_4") (pintype "passive"))
    )
    (net (code "37") (name "Net-(U1-BOOT0)") (class "Default")
      (node (ref "R2") (pin "2") (pinfunction "2_2") (pintype "passive"))
      (node (ref "U1") (pin "60") (pinfunction "BOOT0_60") (pintype "input"))
    )
    (net (code "38") (name "Net-(U1-OSC_IN{slash}PD0)") (class "Default")
      (node (ref "U1") (pin "5") (pinfunction "OSC_IN/PD0_5") (pintype "input"))
      (node (ref "X1") (pin "1") (pinfunction "OSC1_1") (pintype "passive"))
    )
    (net (code "39") (name "Net-(U1-OSC_OUT{slash}PD1)") (class "Default")
      (node (ref "R1") (pin "2") (pinfunction "2_2") (pintype "passive"))
      (node (ref "U1") (pin "6") (pinfunction "OSC_OUT/PD1_6") (pintype "output"))
    )
    (net (code "40") (name "Net-(U1-PA1)") (class "Default")
      (node (ref "C11") (pin "1") (pinfunction "1_1") (pintype "passive"))
      (node (ref "R10") (pin "2") (pinfunction "2_2") (pintype "passive"))
      (node (ref "U1") (pin "15") (pinfunction "PA1_15") (pintype "bidirectional"))
    )
    (net (code "41") (name "Net-(U1-PA2)") (class "Default")
      (node (ref "C12") (pin "2") (pinfunction "2_2") (pintype "passive"))
      (node (ref "R11") (pin "2") (pinfunction "2_2") (pintype "passive"))
      (node (ref "U1") (pin "16") (pinfunction "PA2_16") (pintype "bidirectional"))
    )
    (net (code "42") (name "Net-(U1-PA3)") (class "Default")
      (node (ref "C13") (pin "2") (pinfunction "2_2") (pintype "passive"))
      (node (ref "R12") (pin "2") (pinfunction "2_2") (pintype "passive"))
      (node (ref "U1") (pin "17") (pinfunction "PA3_17") (pintype "bidirectional"))
    )
    (net (code "43") (name "Net-(U1-VDDA)") (class "Default")
      (node (ref "C6") (pin "2") (pinfunction "2_2") (pintype "passive"))
      (node (ref "C7") (pin "2") (pinfunction "2_2") (pintype "passive"))
      (node (ref "L6") (pin "2") (pinfunction "2_2") (pintype "passive"))
      (node (ref "U1") (pin "13") (pinfunction "VDDA_13") (pintype "power_in"))
    )
    (net (code "44") (name "Net-(U2-BP)") (class "Default")
      (node (ref "C21") (pin "2") (pinfunction "2_2") (pintype "passive"))
      (node (ref "U2") (pin "4") (pinfunction "BP_4") (pintype "passive"))
    )
    (net (code "45") (name "Net-(U4-BST)") (class "Default")
      (node (ref "C19") (pin "1") (pinfunction "1_1") (pintype "passive"))
      (node (ref "U4") (pin "8") (pinfunction "BST_8") (pintype "passive"))
    )
    (net (code "46") (name "Net-(U4-COMP)") (class "Default")
      (node (ref "C18") (pin "1") (pinfunction "1_1") (pintype "passive"))
      (node (ref "U4") (pin "3") (pinfunction "COMP_3") (pintype "passive"))
    )
    (net (code "47") (name "Net-(U4-FB)") (class "Default")
      (node (ref "R20") (pin "1") (pinfunction "1_1") (pintype "passive"))
      (node (ref "R21") (pin "2") (pinfunction "2_2") (pintype "passive"))
      (node (ref "U4") (pin "4") (pinfunction "FB_4") (pintype "passive"))
    )
    (net (code "48") (name "Net-(U4-FREQ)") (class "Default")
      (node (ref "R19") (pin "2") (pinfunction "2_2") (pintype "passive"))
      (node (ref "U4") (pin "6") (pinfunction "FREQ_6") (pintype "passive"))
    )
    (net (code "49") (name "Net-(U5-RFO)") (class "Default")
      (node (ref "C15") (pin "1") (pinfunction "1_1") (pintype "passive"))
      (node (ref "L1") (pin "1") (pinfunction "1_1") (pintype "passive"))
      (node (ref "U5") (pin "5") (pinfunction "RFO_5") (pintype "passive"))
    )
    (net (code "50") (name "Net-(U5-XTAL)") (class "Default")
      (node (ref "U5") (pin "1") (pinfunction "XTAL_1") (pintype "passive"))
      (node (ref "X2") (pin "1") (pintype "passive"))
    )
    (net (code "51") (name "Net-(U10-+IN)") (class "Default")
      (node (ref "R15") (pin "1") (pinfunction "1_1") (pintype "passive"))
      (node (ref "U10") (pin "1") (pinfunction "+IN_1") (pintype "passive"))
      (node (ref "U9") (pin "4") (pinfunction "B_4") (pintype "passive"))
      (node (ref "U9") (pin "6") (pinfunction "B_6") (pintype "passive"))
    )
    (net (code "52") (name "Net-(U12-+IN)") (class "Default")
      (node (ref "R26") (pin "2") (pintype "passive"))
      (node (ref "U12") (pin "1") (pinfunction "+IN_1") (pintype "passive"))
    )
    (net (code "53") (name "Net-(U12--IN)") (class "Default")
      (node (ref "C27") (pin "2") (pinfunction "2_2") (pintype "passive"))
      (node (ref "R28") (pin "2") (pinfunction "2_2") (pintype "passive"))
      (node (ref "R29") (pin "1") (pinfunction "1_1") (pintype "passive"))
      (node (ref "U12") (pin "3") (pinfunction "-IN_3") (pintype "passive"))
    )
    (net (code "54") (name "Net-(U13-BP)") (class "Default")
      (node (ref "C41") (pin "2") (pinfunction "2_2") (pintype "passive"))
      (node (ref "U13") (pin "4") (pinfunction "BP_4") (pintype "passive"))
    )
    (net (code "55") (name "Net-(U14-A)") (class "Default")
      (node (ref "R47") (pin "2") (pinfunction "2_2") (pintype "passive"))
      (node (ref "RS485") (pin "2") (pinfunction "2_2") (pintype "passive"))
      (node (ref "U14") (pin "6") (pinfunction "A_6") (pintype "passive"))
    )
    (net (code "56") (name "Net-(U14-B)") (class "Default")
      (node (ref "R47") (pin "1") (pinfunction "1_1") (pintype "passive"))
      (node (ref "RS485") (pin "1") (pinfunction "1_1") (pintype "passive"))
      (node (ref "U14") (pin "7") (pinfunction "B_7") (pintype "passive"))
    )
    (net (code "57") (name "Net-(X1-OSC2)") (class "Default")
      (node (ref "R1") (pin "1") (pinfunction "1_1") (pintype "passive"))
      (node (ref "X1") (pin "3") (pinfunction "OSC2_3") (pintype "passive"))
    )
    (net (code "58") (name "unconnected-(DLOAD-D--Pad2)") (class "Default")
      (node (ref "DLOAD") (pin "2") (pinfunction "D-_2") (pintype "passive"))
    )
    (net (code "59") (name "unconnected-(U1-NRST-Pad7)") (class "Default")
      (node (ref "U1") (pin "7") (pinfunction "NRST_7") (pintype "bidirectional"))
    )
    (net (code "60") (name "unconnected-(U1-PA0-WKUP-Pad14)") (class "Default")
      (node (ref "U1") (pin "14") (pinfunction "PA0-WKUP_14") (pintype "bidirectional"))
    )
    (net (code "61") (name "unconnected-(U1-PA4-Pad20)") (class "Default")
      (node (ref "U1") (pin "20") (pinfunction "PA4_20") (pintype "bidirectional"))
    )
    (net (code "62") (name "unconnected-(U1-PA5-Pad21)") (class "Default")
      (node (ref "U1") (pin "21") (pinfunction "PA5_21") (pintype "bidirectional"))
    )
    (net (code "63") (name "unconnected-(U1-PA6-Pad22)") (class "Default")
      (node (ref "U1") (pin "22") (pinfunction "PA6_22") (pintype "bidirectional"))
    )
    (net (code "64") (name "unconnected-(U1-PA7-Pad23)") (class "Default")
      (node (ref "U1") (pin "23") (pinfunction "PA7_23") (pintype "bidirectional"))
    )
    (net (code "65") (name "unconnected-(U1-PA8-Pad41)") (class "Default")
      (node (ref "U1") (pin "41") (pinfunction "PA8_41") (pintype "bidirectional"))
    )
    (net (code "66") (name "unconnected-(U1-PA12-Pad45)") (class "Default")
      (node (ref "U1") (pin "45") (pinfunction "PA12_45") (pintype "bidirectional"))
    )
    (net (code "67") (name "unconnected-(U1-PA15{slash}JTDI-Pad50)") (class "Default")
      (node (ref "U1") (pin "50") (pinfunction "PA15/JTDI_50") (pintype "bidirectional"))
    )
    (net (code "68") (name "unconnected-(U1-PB2{slash}BOOT1-Pad28)") (class "Default")
      (node (ref "U1") (pin "28") (pinfunction "PB2/BOOT1_28") (pintype "bidirectional"))
    )
    (net (code "69") (name "unconnected-(U1-PB3{slash}JTDO-Pad55)") (class "Default")
      (node (ref "U1") (pin "55") (pinfunction "PB3/JTDO_55") (pintype "bidirectional"))
    )
    (net (code "70") (name "unconnected-(U1-PB4{slash}JNTRST-Pad56)") (class "Default")
      (node (ref "U1") (pin "56") (pinfunction "PB4/JNTRST_56") (pintype "bidirectional"))
    )
    (net (code "71") (name "unconnected-(U1-PB5-Pad57)") (class "Default")
      (node (ref "U1") (pin "57") (pinfunction "PB5_57") (pintype "bidirectional"))
    )
    (net (code "72") (name "unconnected-(U1-PB7-Pad59)") (class "Default")
      (node (ref "U1") (pin "59") (pinfunction "PB7_59") (pintype "bidirectional"))
    )
    (net (code "73") (name "unconnected-(U1-PB8-Pad61)") (class "Default")
      (node (ref "U1") (pin "61") (pinfunction "PB8_61") (pintype "bidirectional"))
    )
    (net (code "74") (name "unconnected-(U1-PB9-Pad62)") (class "Default")
      (node (ref "U1") (pin "62") (pinfunction "PB9_62") (pintype "bidirectional"))
    )
    (net (code "75") (name "unconnected-(U1-PB14-Pad35)") (class "Default")
      (node (ref "U1") (pin "35") (pinfunction "PB14_35") (pintype "bidirectional"))
    )
    (net (code "76") (name "unconnected-(U1-PB15-Pad36)") (class "Default")
      (node (ref "U1") (pin "36") (pinfunction "PB15_36") (pintype "bidirectional"))
    )
    (net (code "77") (name "unconnected-(U1-PC0-Pad8)") (class "Default")
      (node (ref "U1") (pin "8") (pinfunction "PC0_8") (pintype "bidirectional"))
    )
    (net (code "78") (name "unconnected-(U1-PC1-Pad9)") (class "Default")
      (node (ref "U1") (pin "9") (pinfunction "PC1_9") (pintype "bidirectional"))
    )
    (net (code "79") (name "unconnected-(U1-PC2-Pad10)") (class "Default")
      (node (ref "U1") (pin "10") (pinfunction "PC2_10") (pintype "bidirectional"))
    )
    (net (code "80") (name "unconnected-(U1-PC3-Pad11)") (class "Default")
      (node (ref "U1") (pin "11") (pinfunction "PC3_11") (pintype "bidirectional"))
    )
    (net (code "81") (name "unconnected-(U1-PC4-Pad24)") (class "Default")
      (node (ref "U1") (pin "24") (pinfunction "PC4_24") (pintype "bidirectional"))
    )
    (net (code "82") (name "unconnected-(U1-PC5-Pad25)") (class "Default")
      (node (ref "U1") (pin "25") (pinfunction "PC5_25") (pintype "bidirectional"))
    )
    (net (code "83") (name "unconnected-(U1-PC6-Pad37)") (class "Default")
      (node (ref "U1") (pin "37") (pinfunction "PC6_37") (pintype "bidirectional"))
    )
    (net (code "84") (name "unconnected-(U1-PC7-Pad38)") (class "Default")
      (node (ref "U1") (pin "38") (pinfunction "PC7_38") (pintype "bidirectional"))
    )
    (net (code "85") (name "unconnected-(U1-PC8-Pad39)") (class "Default")
      (node (ref "U1") (pin "39") (pinfunction "PC8_39") (pintype "bidirectional"))
    )
    (net (code "86") (name "unconnected-(U1-PC9-Pad40)") (class "Default")
      (node (ref "U1") (pin "40") (pinfunction "PC9_40") (pintype "bidirectional"))
    )
    (net (code "87") (name "unconnected-(U1-PC10-Pad51)") (class "Default")
      (node (ref "U1") (pin "51") (pinfunction "PC10_51") (pintype "bidirectional"))
    )
    (net (code "88") (name "unconnected-(U1-PC11-Pad52)") (class "Default")
      (node (ref "U1") (pin "52") (pinfunction "PC11_52") (pintype "bidirectional"))
    )
    (net (code "89") (name "unconnected-(U1-PC12-Pad53)") (class "Default")
      (node (ref "U1") (pin "53") (pinfunction "PC12_53") (pintype "bidirectional"))
    )
    (net (code "90") (name "unconnected-(U1-PC15-OSC32_OUT-Pad4)") (class "Default")
      (node (ref "U1") (pin "4") (pinfunction "PC15-OSC32_OUT_4") (pintype "bidirectional"))
    )
    (net (code "91") (name "unconnected-(U1-PD2-Pad54)") (class "Default")
      (node (ref "U1") (pin "54") (pinfunction "PD2_54") (pintype "bidirectional"))
    )
    (net (code "92") (name "unconnected-(U1-VBAT-Pad1)") (class "Default")
      (node (ref "U1") (pin "1") (pinfunction "VBAT_1") (pintype "power_in"))
    )
    (net (code "93") (name "unconnected-(U4-EN-Pad2)") (class "Default")
      (node (ref "U4") (pin "2") (pinfunction "EN_2") (pintype "passive"))
    )
    (net (code "94") (name "unconnected-(U8-NC-Pad3)") (class "Default")
      (node (ref "U8") (pin "3") (pinfunction "NC_3") (pintype "passive"))
    )
    (net (code "95") (name "unconnected-(U8-NC-Pad4)") (class "Default")
      (node (ref "U8") (pin "4") (pinfunction "NC_4") (pintype "passive"))
    )
  )
)
